# DDRmem.net
KiCad netlist of a schematic drawn in Altium Designer
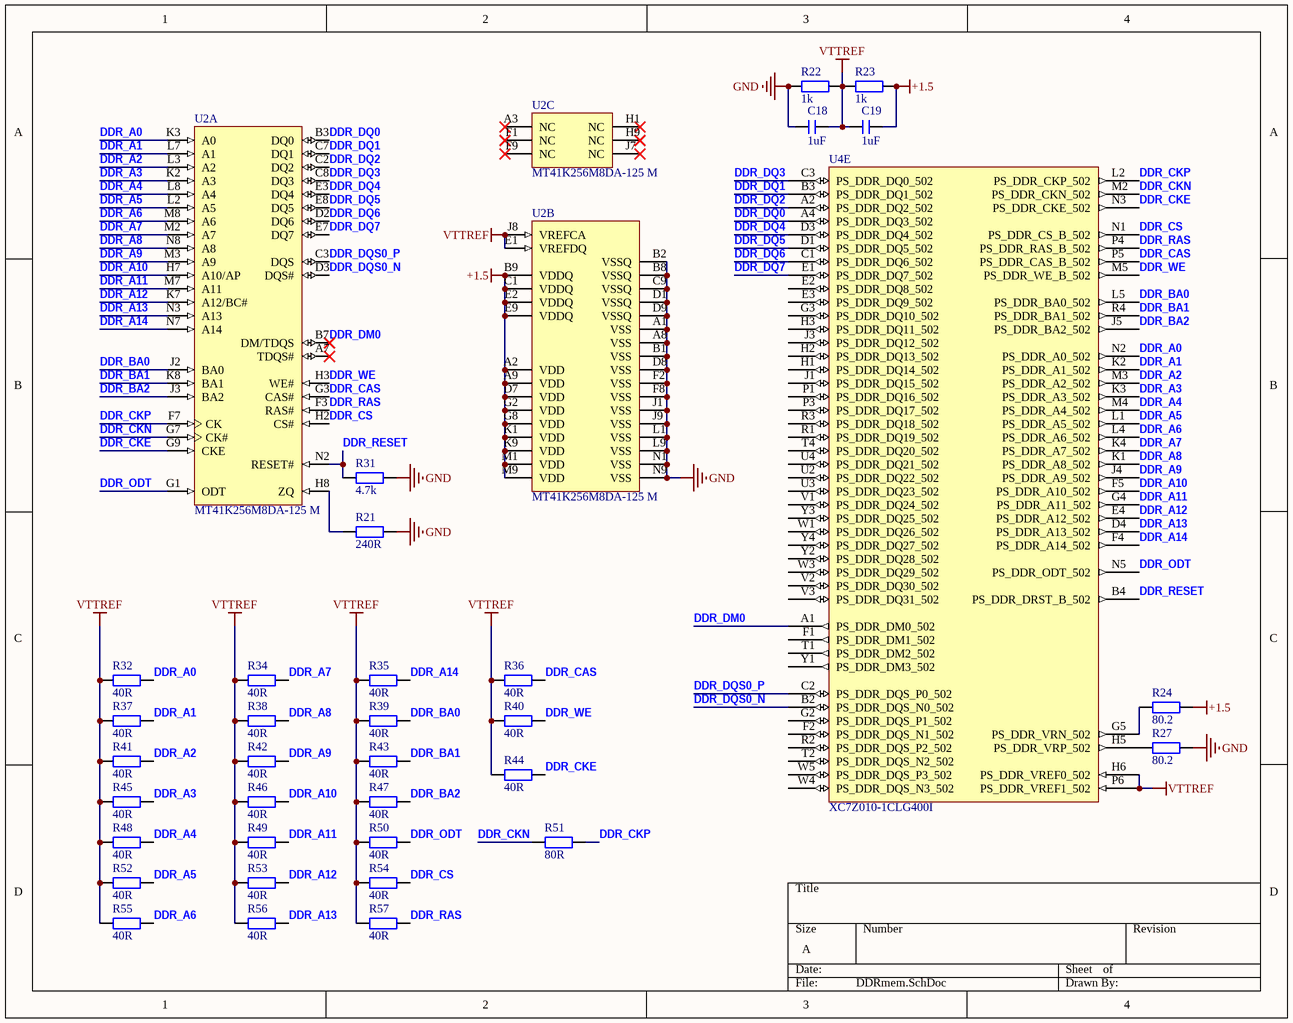
[diagram p0: DDRmem.SchDoc]

(export (version "E")
  (design (tool "Eeschema 10.0.6"))
  (components
    (comp (ref "C18")
      (value "1uF")
      (footprint "SamacSys:CAP_0201")
      (description "无极性贴片电容")
      (fields (field (name "版权归属") "源创客"))
      (libsource (lib "源创客") (part "C"))
    )
    (comp (ref "C19")
      (value "1uF")
      (footprint "SamacSys:CAP_0201")
      (description "无极性贴片电容")
      (fields (field (name "版权归属") "源创客"))
      (libsource (lib "源创客") (part "C"))
    )
    (comp (ref "R21")
      (value "240R")
      (footprint "SamacSys:RES_0201")
      (description "贴片电阻")
      (fields (field (name "版权归属") "源创客"))
      (libsource (lib "源创客") (part "R"))
    )
    (comp (ref "R22")
      (value "1k")
      (footprint "SamacSys:RES_0201")
      (description "贴片电阻")
      (fields (field (name "版权归属") "源创客"))
      (libsource (lib "源创客") (part "R"))
    )
    (comp (ref "R23")
      (value "1k")
      (footprint "SamacSys:RES_0201")
      (description "贴片电阻")
      (fields (field (name "版权归属") "源创客"))
      (libsource (lib "源创客") (part "R"))
    )
    (comp (ref "R24")
      (value "80.2")
      (footprint "SamacSys:RES_0201")
      (description "贴片电阻")
      (fields (field (name "版权归属") "源创客"))
      (libsource (lib "源创客") (part "R"))
    )
    (comp (ref "R27")
      (value "80.2")
      (footprint "SamacSys:RES_0201")
      (description "贴片电阻")
      (fields (field (name "版权归属") "源创客"))
      (libsource (lib "源创客") (part "R"))
    )
    (comp (ref "R31")
      (value "4.7k")
      (footprint "SamacSys:RES_0402")
      (description "贴片电阻")
      (fields (field (name "版权归属") "源创客"))
      (libsource (lib "源创客") (part "R"))
    )
    (comp (ref "R32")
      (value "40R")
      (footprint "SamacSys:RES_0201")
      (description "贴片电阻")
      (fields (field (name "版权归属") "源创客"))
      (libsource (lib "源创客") (part "R"))
    )
    (comp (ref "R34")
      (value "40R")
      (footprint "SamacSys:RES_0201")
      (description "贴片电阻")
      (fields (field (name "版权归属") "源创客"))
      (libsource (lib "源创客") (part "R"))
    )
    (comp (ref "R35")
      (value "40R")
      (footprint "SamacSys:RES_0201")
      (description "贴片电阻")
      (fields (field (name "版权归属") "源创客"))
      (libsource (lib "源创客") (part "R"))
    )
    (comp (ref "R36")
      (value "40R")
      (footprint "SamacSys:RES_0201")
      (description "贴片电阻")
      (fields (field (name "版权归属") "源创客"))
      (libsource (lib "源创客") (part "R"))
    )
    (comp (ref "R37")
      (value "40R")
      (footprint "SamacSys:RES_0201")
      (description "贴片电阻")
      (fields (field (name "版权归属") "源创客"))
      (libsource (lib "源创客") (part "R"))
    )
    (comp (ref "R38")
      (value "40R")
      (footprint "SamacSys:RES_0201")
      (description "贴片电阻")
      (fields (field (name "版权归属") "源创客"))
      (libsource (lib "源创客") (part "R"))
    )
    (comp (ref "R39")
      (value "40R")
      (footprint "SamacSys:RES_0201")
      (description "贴片电阻")
      (fields (field (name "版权归属") "源创客"))
      (libsource (lib "源创客") (part "R"))
    )
    (comp (ref "R40")
      (value "40R")
      (footprint "SamacSys:RES_0201")
      (description "贴片电阻")
      (fields (field (name "版权归属") "源创客"))
      (libsource (lib "源创客") (part "R"))
    )
    (comp (ref "R41")
      (value "40R")
      (footprint "SamacSys:RES_0201")
      (description "贴片电阻")
      (fields (field (name "版权归属") "源创客"))
      (libsource (lib "源创客") (part "R"))
    )
    (comp (ref "R42")
      (value "40R")
      (footprint "SamacSys:RES_0201")
      (description "贴片电阻")
      (fields (field (name "版权归属") "源创客"))
      (libsource (lib "源创客") (part "R"))
    )
    (comp (ref "R43")
      (value "40R")
      (footprint "SamacSys:RES_0201")
      (description "贴片电阻")
      (fields (field (name "版权归属") "源创客"))
      (libsource (lib "源创客") (part "R"))
    )
    (comp (ref "R44")
      (value "40R")
      (footprint "SamacSys:RES_0201")
      (description "贴片电阻")
      (fields (field (name "版权归属") "源创客"))
      (libsource (lib "源创客") (part "R"))
    )
    (comp (ref "R45")
      (value "40R")
      (footprint "SamacSys:RES_0201")
      (description "贴片电阻")
      (fields (field (name "版权归属") "源创客"))
      (libsource (lib "源创客") (part "R"))
    )
    (comp (ref "R46")
      (value "40R")
      (footprint "SamacSys:RES_0201")
      (description "贴片电阻")
      (fields (field (name "版权归属") "源创客"))
      (libsource (lib "源创客") (part "R"))
    )
    (comp (ref "R47")
      (value "40R")
      (footprint "SamacSys:RES_0201")
      (description "贴片电阻")
      (fields (field (name "版权归属") "源创客"))
      (libsource (lib "源创客") (part "R"))
    )
    (comp (ref "R48")
      (value "40R")
      (footprint "SamacSys:RES_0201")
      (description "贴片电阻")
      (fields (field (name "版权归属") "源创客"))
      (libsource (lib "源创客") (part "R"))
    )
    (comp (ref "R49")
      (value "40R")
      (footprint "SamacSys:RES_0201")
      (description "贴片电阻")
      (fields (field (name "版权归属") "源创客"))
      (libsource (lib "源创客") (part "R"))
    )
    (comp (ref "R50")
      (value "40R")
      (footprint "SamacSys:RES_0201")
      (description "贴片电阻")
      (fields (field (name "版权归属") "源创客"))
      (libsource (lib "源创客") (part "R"))
    )
    (comp (ref "R51")
      (value "80R")
      (footprint "SamacSys:RES_0201")
      (description "贴片电阻")
      (fields (field (name "版权归属") "源创客"))
      (libsource (lib "源创客") (part "R"))
    )
    (comp (ref "R52")
      (value "40R")
      (footprint "SamacSys:RES_0201")
      (description "贴片电阻")
      (fields (field (name "版权归属") "源创客"))
      (libsource (lib "源创客") (part "R"))
    )
    (comp (ref "R53")
      (value "40R")
      (footprint "SamacSys:RES_0201")
      (description "贴片电阻")
      (fields (field (name "版权归属") "源创客"))
      (libsource (lib "源创客") (part "R"))
    )
    (comp (ref "R54")
      (value "40R")
      (footprint "SamacSys:RES_0201")
      (description "贴片电阻")
      (fields (field (name "版权归属") "源创客"))
      (libsource (lib "源创客") (part "R"))
    )
    (comp (ref "R55")
      (value "40R")
      (footprint "SamacSys:RES_0201")
      (description "贴片电阻")
      (fields (field (name "版权归属") "源创客"))
      (libsource (lib "源创客") (part "R"))
    )
    (comp (ref "R56")
      (value "40R")
      (footprint "SamacSys:RES_0201")
      (description "贴片电阻")
      (fields (field (name "版权归属") "源创客"))
      (libsource (lib "源创客") (part "R"))
    )
    (comp (ref "R57")
      (value "40R")
      (footprint "SamacSys:RES_0201")
      (description "贴片电阻")
      (fields (field (name "版权归属") "源创客"))
      (libsource (lib "源创客") (part "R"))
    )
    (comp (ref "U2")
      (value "MT41K256M8DA-125 M")
      (footprint "MICT-DA-78")
      (description "2Gb DDR3-1600 SDRAM, 256Mb x 8, 1.25ns, 1.35V, 0 to 95 degC, 78-Ball FBGA")
      (fields (field (name "MANUFACTURER") "Micron") (field (name "VOLTAGE") "1.35VÂ"))
      (libsource (lib "Altium Content Vault") (part "MICT-MT41K256M8DA-78"))
    )
    (comp (ref "U4")
      (value "XC7Z010-1CLG400I")
      (footprint "CLG400")
      (fields (field (name "GENERIC PART NUMBER") "XC7Z010"))
      (libsource (lib "Altium Content Vault") (part "XNLX-XC7Z010-CLG400"))
    )
  )
  (nets
    (net (code "1") (name "+1.5") (class "Default")
      (node (ref "C19") (pin "1") (pinfunction "1_1") (pintype "passive"))
      (node (ref "R23") (pin "1") (pinfunction "1_1") (pintype "passive"))
      (node (ref "R24") (pin "1") (pinfunction "1_1") (pintype "passive"))
      (node (ref "U2") (pin "A2") (pinfunction "VDD_A2") (pintype "power_in"))
      (node (ref "U2") (pin "A9") (pinfunction "VDD_A9") (pintype "power_in"))
      (node (ref "U2") (pin "B9") (pinfunction "VDDQ_B9") (pintype "power_in"))
      (node (ref "U2") (pin "C1") (pinfunction "VDDQ_C1") (pintype "power_in"))
      (node (ref "U2") (pin "D7") (pinfunction "VDD_D7") (pintype "power_in"))
      (node (ref "U2") (pin "E2") (pinfunction "VDDQ_E2") (pintype "power_in"))
      (node (ref "U2") (pin "E9") (pinfunction "VDDQ_E9") (pintype "power_in"))
      (node (ref "U2") (pin "G2") (pinfunction "VDD_G2") (pintype "power_in"))
      (node (ref "U2") (pin "G8") (pinfunction "VDD_G8") (pintype "power_in"))
      (node (ref "U2") (pin "K1") (pinfunction "VDD_K1") (pintype "power_in"))
      (node (ref "U2") (pin "K9") (pinfunction "VDD_K9") (pintype "power_in"))
      (node (ref "U2") (pin "M1") (pinfunction "VDD_M1") (pintype "power_in"))
      (node (ref "U2") (pin "M9") (pinfunction "VDD_M9") (pintype "power_in"))
    )
    (net (code "2") (name "/DDR_A0") (class "Default")
      (node (ref "R32") (pin "1") (pinfunction "1_1") (pintype "passive"))
      (node (ref "U2") (pin "K3") (pinfunction "A0_K3") (pintype "input"))
      (node (ref "U4") (pin "N2") (pinfunction "PS_DDR_A0_502_N2") (pintype "output"))
    )
    (net (code "3") (name "/DDR_A1") (class "Default")
      (node (ref "R37") (pin "1") (pinfunction "1_1") (pintype "passive"))
      (node (ref "U2") (pin "L7") (pinfunction "A1_L7") (pintype "input"))
      (node (ref "U4") (pin "K2") (pinfunction "PS_DDR_A1_502_K2") (pintype "output"))
    )
    (net (code "4") (name "/DDR_A2") (class "Default")
      (node (ref "R41") (pin "1") (pinfunction "1_1") (pintype "passive"))
      (node (ref "U2") (pin "L3") (pinfunction "A2_L3") (pintype "input"))
      (node (ref "U4") (pin "M3") (pinfunction "PS_DDR_A2_502_M3") (pintype "output"))
    )
    (net (code "5") (name "/DDR_A3") (class "Default")
      (node (ref "R45") (pin "1") (pinfunction "1_1") (pintype "passive"))
      (node (ref "U2") (pin "K2") (pinfunction "A3_K2") (pintype "input"))
      (node (ref "U4") (pin "K3") (pinfunction "PS_DDR_A3_502_K3") (pintype "output"))
    )
    (net (code "6") (name "/DDR_A4") (class "Default")
      (node (ref "R48") (pin "1") (pinfunction "1_1") (pintype "passive"))
      (node (ref "U2") (pin "L8") (pinfunction "A4_L8") (pintype "input"))
      (node (ref "U4") (pin "M4") (pinfunction "PS_DDR_A4_502_M4") (pintype "output"))
    )
    (net (code "7") (name "/DDR_A5") (class "Default")
      (node (ref "R52") (pin "1") (pinfunction "1_1") (pintype "passive"))
      (node (ref "U2") (pin "L2") (pinfunction "A5_L2") (pintype "input"))
      (node (ref "U4") (pin "L1") (pinfunction "PS_DDR_A5_502_L1") (pintype "output"))
    )
    (net (code "8") (name "/DDR_A6") (class "Default")
      (node (ref "R55") (pin "1") (pinfunction "1_1") (pintype "passive"))
      (node (ref "U2") (pin "M8") (pinfunction "A6_M8") (pintype "input"))
      (node (ref "U4") (pin "L4") (pinfunction "PS_DDR_A6_502_L4") (pintype "output"))
    )
    (net (code "9") (name "/DDR_A7") (class "Default")
      (node (ref "R34") (pin "1") (pinfunction "1_1") (pintype "passive"))
      (node (ref "U2") (pin "M2") (pinfunction "A7_M2") (pintype "input"))
      (node (ref "U4") (pin "K4") (pinfunction "PS_DDR_A7_502_K4") (pintype "output"))
    )
    (net (code "10") (name "/DDR_A8") (class "Default")
      (node (ref "R38") (pin "1") (pinfunction "1_1") (pintype "passive"))
      (node (ref "U2") (pin "N8") (pinfunction "A8_N8") (pintype "input"))
      (node (ref "U4") (pin "K1") (pinfunction "PS_DDR_A8_502_K1") (pintype "output"))
    )
    (net (code "11") (name "/DDR_A9") (class "Default")
      (node (ref "R42") (pin "1") (pinfunction "1_1") (pintype "passive"))
      (node (ref "U2") (pin "M3") (pinfunction "A9_M3") (pintype "input"))
      (node (ref "U4") (pin "J4") (pinfunction "PS_DDR_A9_502_J4") (pintype "output"))
    )
    (net (code "12") (name "/DDR_A10") (class "Default")
      (node (ref "R46") (pin "1") (pinfunction "1_1") (pintype "passive"))
      (node (ref "U2") (pin "H7") (pinfunction "A10/AP_H7") (pintype "input"))
      (node (ref "U4") (pin "F5") (pinfunction "PS_DDR_A10_502_F5") (pintype "output"))
    )
    (net (code "13") (name "/DDR_A11") (class "Default")
      (node (ref "R49") (pin "1") (pinfunction "1_1") (pintype "passive"))
      (node (ref "U2") (pin "M7") (pinfunction "A11_M7") (pintype "input"))
      (node (ref "U4") (pin "G4") (pinfunction "PS_DDR_A11_502_G4") (pintype "output"))
    )
    (net (code "14") (name "/DDR_A12") (class "Default")
      (node (ref "R53") (pin "1") (pinfunction "1_1") (pintype "passive"))
      (node (ref "U2") (pin "K7") (pinfunction "A12/BC#_K7") (pintype "input"))
      (node (ref "U4") (pin "E4") (pinfunction "PS_DDR_A12_502_E4") (pintype "output"))
    )
    (net (code "15") (name "/DDR_A13") (class "Default")
      (node (ref "R56") (pin "1") (pinfunction "1_1") (pintype "passive"))
      (node (ref "U2") (pin "N3") (pinfunction "A13_N3") (pintype "input"))
      (node (ref "U4") (pin "D4") (pinfunction "PS_DDR_A13_502_D4") (pintype "output"))
    )
    (net (code "16") (name "/DDR_A14") (class "Default")
      (node (ref "R35") (pin "1") (pinfunction "1_1") (pintype "passive"))
      (node (ref "U2") (pin "N7") (pinfunction "A14_N7") (pintype "input"))
      (node (ref "U4") (pin "F4") (pinfunction "PS_DDR_A14_502_F4") (pintype "output"))
    )
    (net (code "17") (name "/DDR_BA0") (class "Default")
      (node (ref "R39") (pin "1") (pinfunction "1_1") (pintype "passive"))
      (node (ref "U2") (pin "J2") (pinfunction "BA0_J2") (pintype "input"))
      (node (ref "U4") (pin "L5") (pinfunction "PS_DDR_BA0_502_L5") (pintype "output"))
    )
    (net (code "18") (name "/DDR_BA1") (class "Default")
      (node (ref "R43") (pin "1") (pinfunction "1_1") (pintype "passive"))
      (node (ref "U2") (pin "K8") (pinfunction "BA1_K8") (pintype "input"))
      (node (ref "U4") (pin "R4") (pinfunction "PS_DDR_BA1_502_R4") (pintype "output"))
    )
    (net (code "19") (name "/DDR_BA2") (class "Default")
      (node (ref "R47") (pin "1") (pinfunction "1_1") (pintype "passive"))
      (node (ref "U2") (pin "J3") (pinfunction "BA2_J3") (pintype "input"))
      (node (ref "U4") (pin "J5") (pinfunction "PS_DDR_BA2_502_J5") (pintype "output"))
    )
    (net (code "20") (name "/DDR_CAS") (class "Default")
      (node (ref "R36") (pin "1") (pinfunction "1_1") (pintype "passive"))
      (node (ref "U2") (pin "G3") (pinfunction "CAS#_G3") (pintype "input"))
      (node (ref "U4") (pin "P5") (pinfunction "PS_DDR_CAS_B_502_P5") (pintype "output"))
    )
    (net (code "21") (name "/DDR_CKE") (class "Default")
      (node (ref "R44") (pin "1") (pinfunction "1_1") (pintype "passive"))
      (node (ref "U2") (pin "G9") (pinfunction "CKE_G9") (pintype "input"))
      (node (ref "U4") (pin "N3") (pinfunction "PS_DDR_CKE_502_N3") (pintype "output"))
    )
    (net (code "22") (name "/DDR_CKN") (class "Default")
      (node (ref "R51") (pin "2") (pinfunction "2_2") (pintype "passive"))
      (node (ref "U2") (pin "G7") (pinfunction "CK#_G7") (pintype "input"))
      (node (ref "U4") (pin "M2") (pinfunction "PS_DDR_CKN_502_M2") (pintype "output"))
    )
    (net (code "23") (name "/DDR_CKP") (class "Default")
      (node (ref "R51") (pin "1") (pinfunction "1_1") (pintype "passive"))
      (node (ref "U2") (pin "F7") (pinfunction "CK_F7") (pintype "input"))
      (node (ref "U4") (pin "L2") (pinfunction "PS_DDR_CKP_502_L2") (pintype "output"))
    )
    (net (code "24") (name "/DDR_CS") (class "Default")
      (node (ref "R54") (pin "1") (pinfunction "1_1") (pintype "passive"))
      (node (ref "U2") (pin "H2") (pinfunction "CS#_H2") (pintype "input"))
      (node (ref "U4") (pin "N1") (pinfunction "PS_DDR_CS_B_502_N1") (pintype "output"))
    )
    (net (code "25") (name "/DDR_DM0") (class "Default")
      (node (ref "U2") (pin "B7") (pinfunction "DM/TDQS_B7") (pintype "bidirectional"))
      (node (ref "U4") (pin "A1") (pinfunction "PS_DDR_DM0_502_A1") (pintype "output"))
    )
    (net (code "26") (name "/DDR_DQ0") (class "Default")
      (node (ref "U2") (pin "B3") (pinfunction "DQ0_B3") (pintype "bidirectional"))
      (node (ref "U4") (pin "A4") (pinfunction "PS_DDR_DQ3_502_A4") (pintype "bidirectional"))
    )
    (net (code "27") (name "/DDR_DQ1") (class "Default")
      (node (ref "U2") (pin "C7") (pinfunction "DQ1_C7") (pintype "bidirectional"))
      (node (ref "U4") (pin "B3") (pinfunction "PS_DDR_DQ1_502_B3") (pintype "bidirectional"))
    )
    (net (code "28") (name "/DDR_DQ2") (class "Default")
      (node (ref "U2") (pin "C2") (pinfunction "DQ2_C2") (pintype "bidirectional"))
      (node (ref "U4") (pin "A2") (pinfunction "PS_DDR_DQ2_502_A2") (pintype "bidirectional"))
    )
    (net (code "29") (name "/DDR_DQ3") (class "Default")
      (node (ref "U2") (pin "C8") (pinfunction "DQ3_C8") (pintype "bidirectional"))
      (node (ref "U4") (pin "C3") (pinfunction "PS_DDR_DQ0_502_C3") (pintype "bidirectional"))
    )
    (net (code "30") (name "/DDR_DQ4") (class "Default")
      (node (ref "U2") (pin "E3") (pinfunction "DQ4_E3") (pintype "bidirectional"))
      (node (ref "U4") (pin "D3") (pinfunction "PS_DDR_DQ4_502_D3") (pintype "bidirectional"))
    )
    (net (code "31") (name "/DDR_DQ5") (class "Default")
      (node (ref "U2") (pin "E8") (pinfunction "DQ5_E8") (pintype "bidirectional"))
      (node (ref "U4") (pin "D1") (pinfunction "PS_DDR_DQ5_502_D1") (pintype "bidirectional"))
    )
    (net (code "32") (name "/DDR_DQ6") (class "Default")
      (node (ref "U2") (pin "D2") (pinfunction "DQ6_D2") (pintype "bidirectional"))
      (node (ref "U4") (pin "C1") (pinfunction "PS_DDR_DQ6_502_C1") (pintype "bidirectional"))
    )
    (net (code "33") (name "/DDR_DQ7") (class "Default")
      (node (ref "U2") (pin "E7") (pinfunction "DQ7_E7") (pintype "bidirectional"))
      (node (ref "U4") (pin "E1") (pinfunction "PS_DDR_DQ7_502_E1") (pintype "bidirectional"))
    )
    (net (code "34") (name "/DDR_DQS0_N") (class "Default")
      (node (ref "U2") (pin "D3") (pinfunction "DQS#_D3") (pintype "bidirectional"))
      (node (ref "U4") (pin "B2") (pinfunction "PS_DDR_DQS_N0_502_B2") (pintype "bidirectional"))
    )
    (net (code "35") (name "/DDR_DQS0_P") (class "Default")
      (node (ref "U2") (pin "C3") (pinfunction "DQS_C3") (pintype "bidirectional"))
      (node (ref "U4") (pin "C2") (pinfunction "PS_DDR_DQS_P0_502_C2") (pintype "bidirectional"))
    )
    (net (code "36") (name "/DDR_ODT") (class "Default")
      (node (ref "R50") (pin "1") (pinfunction "1_1") (pintype "passive"))
      (node (ref "U2") (pin "G1") (pinfunction "ODT_G1") (pintype "input"))
      (node (ref "U4") (pin "N5") (pinfunction "PS_DDR_ODT_502_N5") (pintype "output"))
    )
    (net (code "37") (name "/DDR_RAS") (class "Default")
      (node (ref "R57") (pin "1") (pinfunction "1_1") (pintype "passive"))
      (node (ref "U2") (pin "F3") (pinfunction "RAS#_F3") (pintype "input"))
      (node (ref "U4") (pin "P4") (pinfunction "PS_DDR_RAS_B_502_P4") (pintype "output"))
    )
    (net (code "38") (name "/DDR_RESET") (class "Default")
      (node (ref "R31") (pin "2") (pinfunction "2_2") (pintype "passive"))
      (node (ref "U2") (pin "N2") (pinfunction "RESET#_N2") (pintype "input"))
      (node (ref "U4") (pin "B4") (pinfunction "PS_DDR_DRST_B_502_B4") (pintype "output"))
    )
    (net (code "39") (name "/DDR_WE") (class "Default")
      (node (ref "R40") (pin "1") (pinfunction "1_1") (pintype "passive"))
      (node (ref "U2") (pin "H3") (pinfunction "WE#_H3") (pintype "input"))
      (node (ref "U4") (pin "M5") (pinfunction "PS_DDR_WE_B_502_M5") (pintype "output"))
    )
    (net (code "40") (name "GND") (class "Default")
      (node (ref "C18") (pin "2") (pinfunction "2_2") (pintype "passive"))
      (node (ref "R21") (pin "1") (pinfunction "1_1") (pintype "passive"))
      (node (ref "R22") (pin "2") (pinfunction "2_2") (pintype "passive"))
      (node (ref "R27") (pin "1") (pinfunction "1_1") (pintype "passive"))
      (node (ref "R31") (pin "1") (pinfunction "1_1") (pintype "passive"))
      (node (ref "U2") (pin "A1") (pinfunction "VSS_A1") (pintype "power_in"))
      (node (ref "U2") (pin "A8") (pinfunction "VSS_A8") (pintype "power_in"))
      (node (ref "U2") (pin "B1") (pinfunction "VSS_B1") (pintype "power_in"))
      (node (ref "U2") (pin "B2") (pinfunction "VSSQ_B2") (pintype "power_in"))
      (node (ref "U2") (pin "B8") (pinfunction "VSSQ_B8") (pintype "power_in"))
      (node (ref "U2") (pin "C9") (pinfunction "VSSQ_C9") (pintype "power_in"))
      (node (ref "U2") (pin "D1") (pinfunction "VSSQ_D1") (pintype "power_in"))
      (node (ref "U2") (pin "D8") (pinfunction "VSS_D8") (pintype "power_in"))
      (node (ref "U2") (pin "D9") (pinfunction "VSSQ_D9") (pintype "power_in"))
      (node (ref "U2") (pin "F2") (pinfunction "VSS_F2") (pintype "power_in"))
      (node (ref "U2") (pin "F8") (pinfunction "VSS_F8") (pintype "power_in"))
      (node (ref "U2") (pin "J1") (pinfunction "VSS_J1") (pintype "power_in"))
      (node (ref "U2") (pin "J9") (pinfunction "VSS_J9") (pintype "power_in"))
      (node (ref "U2") (pin "L1") (pinfunction "VSS_L1") (pintype "power_in"))
      (node (ref "U2") (pin "L9") (pinfunction "VSS_L9") (pintype "power_in"))
      (node (ref "U2") (pin "N1") (pinfunction "VSS_N1") (pintype "power_in"))
      (node (ref "U2") (pin "N9") (pinfunction "VSS_N9") (pintype "power_in"))
    )
    (net (code "41") (name "Net-(U2A-ZQ)") (class "Default")
      (node (ref "R21") (pin "2") (pinfunction "2_2") (pintype "passive"))
      (node (ref "U2") (pin "H8") (pinfunction "ZQ_H8") (pintype "input"))
    )
    (net (code "42") (name "Net-(U4E-PS_DDR_VRN_502)") (class "Default")
      (node (ref "R24") (pin "2") (pinfunction "2_2") (pintype "passive"))
      (node (ref "U4") (pin "G5") (pinfunction "PS_DDR_VRN_502_G5") (pintype "output"))
    )
    (net (code "43") (name "Net-(U4E-PS_DDR_VRP_502)") (class "Default")
      (node (ref "R27") (pin "2") (pinfunction "2_2") (pintype "passive"))
      (node (ref "U4") (pin "H5") (pinfunction "PS_DDR_VRP_502_H5") (pintype "output"))
    )
    (net (code "44") (name "VTTREF") (class "Default")
      (node (ref "C18") (pin "1") (pinfunction "1_1") (pintype "passive"))
      (node (ref "C19") (pin "2") (pinfunction "2_2") (pintype "passive"))
      (node (ref "R22") (pin "1") (pinfunction "1_1") (pintype "passive"))
      (node (ref "R23") (pin "2") (pinfunction "2_2") (pintype "passive"))
      (node (ref "R32") (pin "2") (pinfunction "2_2") (pintype "passive"))
      (node (ref "R34") (pin "2") (pinfunction "2_2") (pintype "passive"))
      (node (ref "R35") (pin "2") (pinfunction "2_2") (pintype "passive"))
      (node (ref "R36") (pin "2") (pinfunction "2_2") (pintype "passive"))
      (node (ref "R37") (pin "2") (pinfunction "2_2") (pintype "passive"))
      (node (ref "R38") (pin "2") (pinfunction "2_2") (pintype "passive"))
      (node (ref "R39") (pin "2") (pinfunction "2_2") (pintype "passive"))
      (node (ref "R40") (pin "2") (pinfunction "2_2") (pintype "passive"))
      (node (ref "R41") (pin "2") (pinfunction "2_2") (pintype "passive"))
      (node (ref "R42") (pin "2") (pinfunction "2_2") (pintype "passive"))
      (node (ref "R43") (pin "2") (pinfunction "2_2") (pintype "passive"))
      (node (ref "R44") (pin "2") (pinfunction "2_2") (pintype "passive"))
      (node (ref "R45") (pin "2") (pinfunction "2_2") (pintype "passive"))
      (node (ref "R46") (pin "2") (pinfunction "2_2") (pintype "passive"))
      (node (ref "R47") (pin "2") (pinfunction "2_2") (pintype "passive"))
      (node (ref "R48") (pin "2") (pinfunction "2_2") (pintype "passive"))
      (node (ref "R49") (pin "2") (pinfunction "2_2") (pintype "passive"))
      (node (ref "R50") (pin "2") (pinfunction "2_2") (pintype "passive"))
      (node (ref "R52") (pin "2") (pinfunction "2_2") (pintype "passive"))
      (node (ref "R53") (pin "2") (pinfunction "2_2") (pintype "passive"))
      (node (ref "R54") (pin "2") (pinfunction "2_2") (pintype "passive"))
      (node (ref "R55") (pin "2") (pinfunction "2_2") (pintype "passive"))
      (node (ref "R56") (pin "2") (pinfunction "2_2") (pintype "passive"))
      (node (ref "R57") (pin "2") (pinfunction "2_2") (pintype "passive"))
      (node (ref "U2") (pin "E1") (pinfunction "VREFDQ_E1") (pintype "input"))
      (node (ref "U2") (pin "J8") (pinfunction "VREFCA_J8") (pintype "input"))
      (node (ref "U4") (pin "H6") (pinfunction "PS_DDR_VREF0_502_H6") (pintype "input"))
      (node (ref "U4") (pin "P6") (pinfunction "PS_DDR_VREF1_502_P6") (pintype "input"))
    )
    (net (code "45") (name "unconnected-(U2A-TDQS#-PadA7)") (class "Default")
      (node (ref "U2") (pin "A7") (pinfunction "TDQS#_A7") (pintype "bidirectional+no_connect"))
    )
    (net (code "46") (name "unconnected-(U2C-NC-PadA3)") (class "Default")
      (node (ref "U2") (pin "A3") (pinfunction "NC_A3") (pintype "passive+no_connect"))
    )
    (net (code "47") (name "unconnected-(U2C-NC-PadF1)") (class "Default")
      (node (ref "U2") (pin "F1") (pinfunction "NC_F1") (pintype "passive+no_connect"))
    )
    (net (code "48") (name "unconnected-(U2C-NC-PadF9)") (class "Default")
      (node (ref "U2") (pin "F9") (pinfunction "NC_F9") (pintype "passive+no_connect"))
    )
    (net (code "49") (name "unconnected-(U2C-NC-PadH1)") (class "Default")
      (node (ref "U2") (pin "H1") (pinfunction "NC_H1") (pintype "passive+no_connect"))
    )
    (net (code "50") (name "unconnected-(U2C-NC-PadH9)") (class "Default")
      (node (ref "U2") (pin "H9") (pinfunction "NC_H9") (pintype "passive+no_connect"))
    )
    (net (code "51") (name "unconnected-(U2C-NC-PadJ7)") (class "Default")
      (node (ref "U2") (pin "J7") (pinfunction "NC_J7") (pintype "passive+no_connect"))
    )
    (net (code "52") (name "unconnected-(U4E-PS_DDR_DM1_502-PadF1)") (class "Default")
      (node (ref "U4") (pin "F1") (pinfunction "PS_DDR_DM1_502_F1") (pintype "output"))
    )
    (net (code "53") (name "unconnected-(U4E-PS_DDR_DM2_502-PadT1)") (class "Default")
      (node (ref "U4") (pin "T1") (pinfunction "PS_DDR_DM2_502_T1") (pintype "output"))
    )
    (net (code "54") (name "unconnected-(U4E-PS_DDR_DM3_502-PadY1)") (class "Default")
      (node (ref "U4") (pin "Y1") (pinfunction "PS_DDR_DM3_502_Y1") (pintype "output"))
    )
    (net (code "55") (name "unconnected-(U4E-PS_DDR_DQ8_502-PadE2)") (class "Default")
      (node (ref "U4") (pin "E2") (pinfunction "PS_DDR_DQ8_502_E2") (pintype "bidirectional"))
    )
    (net (code "56") (name "unconnected-(U4E-PS_DDR_DQ9_502-PadE3)") (class "Default")
      (node (ref "U4") (pin "E3") (pinfunction "PS_DDR_DQ9_502_E3") (pintype "bidirectional"))
    )
    (net (code "57") (name "unconnected-(U4E-PS_DDR_DQ10_502-PadG3)") (class "Default")
      (node (ref "U4") (pin "G3") (pinfunction "PS_DDR_DQ10_502_G3") (pintype "bidirectional"))
    )
    (net (code "58") (name "unconnected-(U4E-PS_DDR_DQ11_502-PadH3)") (class "Default")
      (node (ref "U4") (pin "H3") (pinfunction "PS_DDR_DQ11_502_H3") (pintype "bidirectional"))
    )
    (net (code "59") (name "unconnected-(U4E-PS_DDR_DQ12_502-PadJ3)") (class "Default")
      (node (ref "U4") (pin "J3") (pinfunction "PS_DDR_DQ12_502_J3") (pintype "bidirectional"))
    )
    (net (code "60") (name "unconnected-(U4E-PS_DDR_DQ13_502-PadH2)") (class "Default")
      (node (ref "U4") (pin "H2") (pinfunction "PS_DDR_DQ13_502_H2") (pintype "bidirectional"))
    )
    (net (code "61") (name "unconnected-(U4E-PS_DDR_DQ14_502-PadH1)") (class "Default")
      (node (ref "U4") (pin "H1") (pinfunction "PS_DDR_DQ14_502_H1") (pintype "bidirectional"))
    )
    (net (code "62") (name "unconnected-(U4E-PS_DDR_DQ15_502-PadJ1)") (class "Default")
      (node (ref "U4") (pin "J1") (pinfunction "PS_DDR_DQ15_502_J1") (pintype "bidirectional"))
    )
    (net (code "63") (name "unconnected-(U4E-PS_DDR_DQ16_502-PadP1)") (class "Default")
      (node (ref "U4") (pin "P1") (pinfunction "PS_DDR_DQ16_502_P1") (pintype "bidirectional"))
    )
    (net (code "64") (name "unconnected-(U4E-PS_DDR_DQ17_502-PadP3)") (class "Default")
      (node (ref "U4") (pin "P3") (pinfunction "PS_DDR_DQ17_502_P3") (pintype "bidirectional"))
    )
    (net (code "65") (name "unconnected-(U4E-PS_DDR_DQ18_502-PadR3)") (class "Default")
      (node (ref "U4") (pin "R3") (pinfunction "PS_DDR_DQ18_502_R3") (pintype "bidirectional"))
    )
    (net (code "66") (name "unconnected-(U4E-PS_DDR_DQ19_502-PadR1)") (class "Default")
      (node (ref "U4") (pin "R1") (pinfunction "PS_DDR_DQ19_502_R1") (pintype "bidirectional"))
    )
    (net (code "67") (name "unconnected-(U4E-PS_DDR_DQ20_502-PadT4)") (class "Default")
      (node (ref "U4") (pin "T4") (pinfunction "PS_DDR_DQ20_502_T4") (pintype "bidirectional"))
    )
    (net (code "68") (name "unconnected-(U4E-PS_DDR_DQ21_502-PadU4)") (class "Default")
      (node (ref "U4") (pin "U4") (pinfunction "PS_DDR_DQ21_502_U4") (pintype "bidirectional"))
    )
    (net (code "69") (name "unconnected-(U4E-PS_DDR_DQ22_502-PadU2)") (class "Default")
      (node (ref "U4") (pin "U2") (pinfunction "PS_DDR_DQ22_502_U2") (pintype "bidirectional"))
    )
    (net (code "70") (name "unconnected-(U4E-PS_DDR_DQ23_502-PadU3)") (class "Default")
      (node (ref "U4") (pin "U3") (pinfunction "PS_DDR_DQ23_502_U3") (pintype "bidirectional"))
    )
    (net (code "71") (name "unconnected-(U4E-PS_DDR_DQ24_502-PadV1)") (class "Default")
      (node (ref "U4") (pin "V1") (pinfunction "PS_DDR_DQ24_502_V1") (pintype "bidirectional"))
    )
    (net (code "72") (name "unconnected-(U4E-PS_DDR_DQ25_502-PadY3)") (class "Default")
      (node (ref "U4") (pin "Y3") (pinfunction "PS_DDR_DQ25_502_Y3") (pintype "bidirectional"))
    )
    (net (code "73") (name "unconnected-(U4E-PS_DDR_DQ26_502-PadW1)") (class "Default")
      (node (ref "U4") (pin "W1") (pinfunction "PS_DDR_DQ26_502_W1") (pintype "bidirectional"))
    )
    (net (code "74") (name "unconnected-(U4E-PS_DDR_DQ27_502-PadY4)") (class "Default")
      (node (ref "U4") (pin "Y4") (pinfunction "PS_DDR_DQ27_502_Y4") (pintype "bidirectional"))
    )
    (net (code "75") (name "unconnected-(U4E-PS_DDR_DQ28_502-PadY2)") (class "Default")
      (node (ref "U4") (pin "Y2") (pinfunction "PS_DDR_DQ28_502_Y2") (pintype "bidirectional"))
    )
    (net (code "76") (name "unconnected-(U4E-PS_DDR_DQ29_502-PadW3)") (class "Default")
      (node (ref "U4") (pin "W3") (pinfunction "PS_DDR_DQ29_502_W3") (pintype "bidirectional"))
    )
    (net (code "77") (name "unconnected-(U4E-PS_DDR_DQ30_502-PadV2)") (class "Default")
      (node (ref "U4") (pin "V2") (pinfunction "PS_DDR_DQ30_502_V2") (pintype "bidirectional"))
    )
    (net (code "78") (name "unconnected-(U4E-PS_DDR_DQ31_502-PadV3)") (class "Default")
      (node (ref "U4") (pin "V3") (pinfunction "PS_DDR_DQ31_502_V3") (pintype "bidirectional"))
    )
    (net (code "79") (name "unconnected-(U4E-PS_DDR_DQS_N1_502-PadF2)") (class "Default")
      (node (ref "U4") (pin "F2") (pinfunction "PS_DDR_DQS_N1_502_F2") (pintype "bidirectional"))
    )
    (net (code "80") (name "unconnected-(U4E-PS_DDR_DQS_N2_502-PadT2)") (class "Default")
      (node (ref "U4") (pin "T2") (pinfunction "PS_DDR_DQS_N2_502_T2") (pintype "bidirectional"))
    )
    (net (code "81") (name "unconnected-(U4E-PS_DDR_DQS_N3_502-PadW4)") (class "Default")
      (node (ref "U4") (pin "W4") (pinfunction "PS_DDR_DQS_N3_502_W4") (pintype "bidirectional"))
    )
    (net (code "82") (name "unconnected-(U4E-PS_DDR_DQS_P1_502-PadG2)") (class "Default")
      (node (ref "U4") (pin "G2") (pinfunction "PS_DDR_DQS_P1_502_G2") (pintype "bidirectional"))
    )
    (net (code "83") (name "unconnected-(U4E-PS_DDR_DQS_P2_502-PadR2)") (class "Default")
      (node (ref "U4") (pin "R2") (pinfunction "PS_DDR_DQS_P2_502_R2") (pintype "bidirectional"))
    )
    (net (code "84") (name "unconnected-(U4E-PS_DDR_DQS_P3_502-PadW5)") (class "Default")
      (node (ref "U4") (pin "W5") (pinfunction "PS_DDR_DQS_P3_502_W5") (pintype "bidirectional"))
    )
  )
)
